# buck-boost.net
KiCad netlist of a schematic drawn in Altium Designer
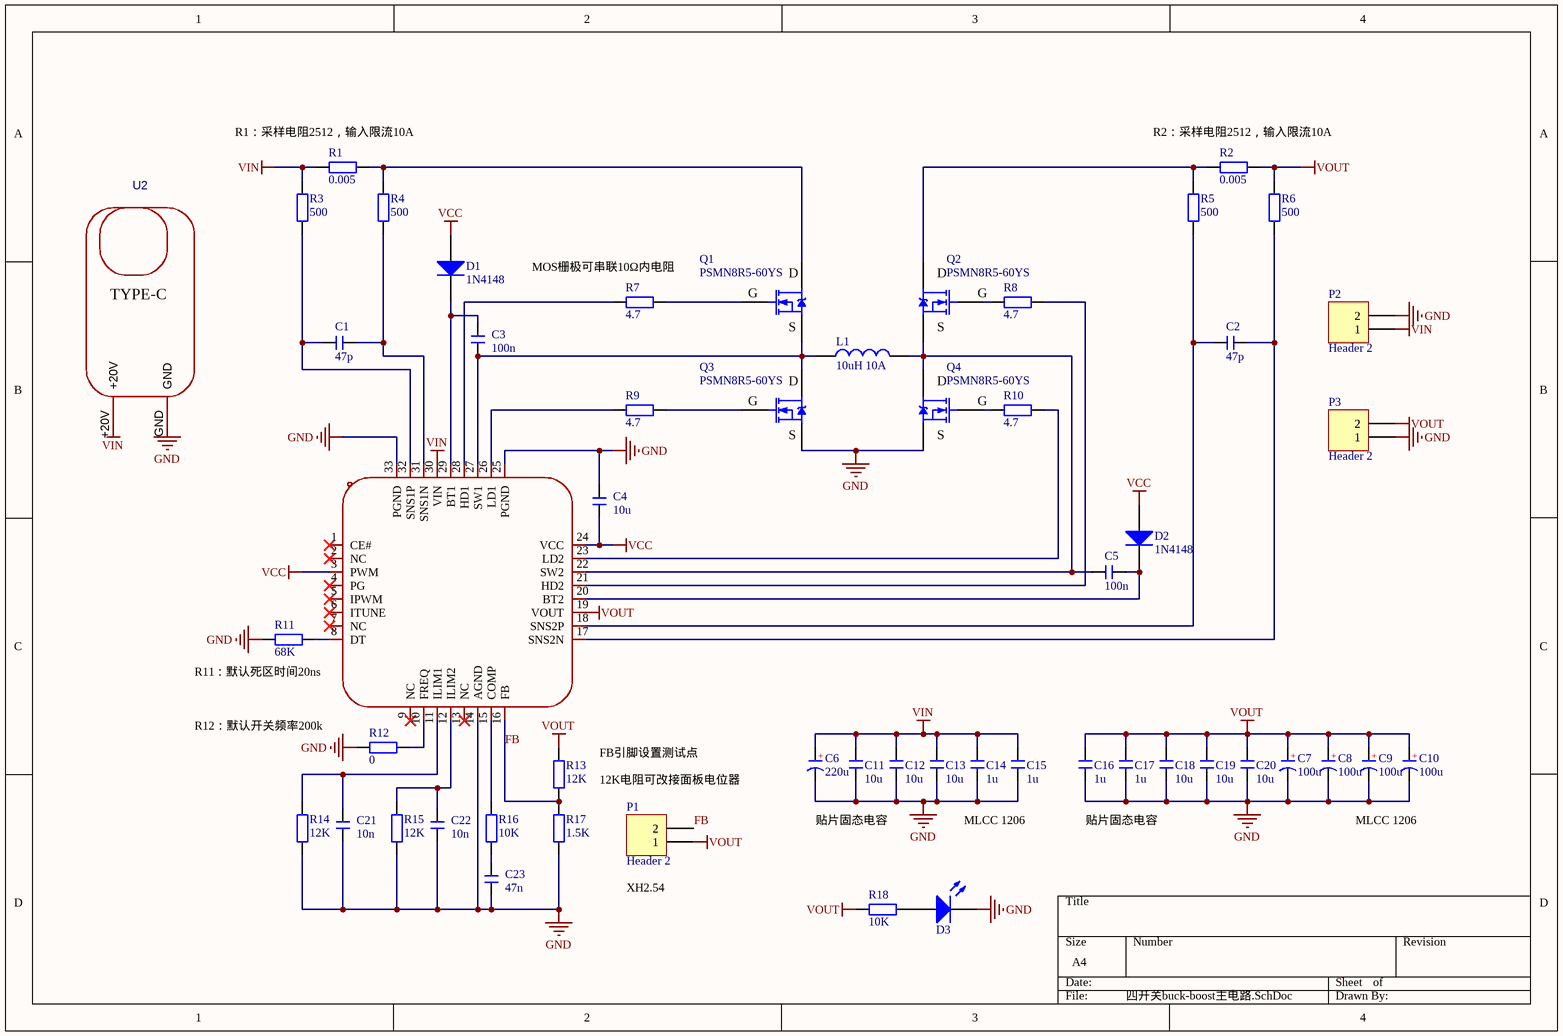
[diagram p0: 四开关buck-boost主电路.SchDoc]

(export (version "E")
  (design (tool "Eeschema 10.0.6"))
  (components
    (comp (ref "C1")
      (value "47p")
      (footprint "C 0603_M")
      (description "贴片电容")
      (libsource (lib "0.1 - 电阻-电容-电感") (part "C"))
    )
    (comp (ref "C2")
      (value "47p")
      (footprint "C 0603_M")
      (description "贴片电容")
      (libsource (lib "0.1 - 电阻-电容-电感") (part "C"))
    )
    (comp (ref "C3")
      (value "100n")
      (footprint "C 0603_M")
      (description "贴片电容")
      (libsource (lib "0.1 - 电阻-电容-电感") (part "C"))
    )
    (comp (ref "C4")
      (value "10u")
      (footprint "C 0603_M")
      (description "贴片电容")
      (libsource (lib "0.1 - 电阻-电容-电感") (part "C"))
    )
    (comp (ref "C5")
      (value "100n")
      (footprint "C 0603_M")
      (description "贴片电容")
      (libsource (lib "0.1 - 电阻-电容-电感") (part "C"))
    )
    (comp (ref "C6")
      (value "220u")
      (footprint "CM F(10*10.2)")
      (description "直插电解电容")
      (libsource (lib "0.1 - 电阻-电容-电感") (part "CE"))
    )
    (comp (ref "C7")
      (value "100u")
      (footprint "CM E(8*10.2)")
      (description "直插电解电容")
      (libsource (lib "0.1 - 电阻-电容-电感") (part "CE"))
    )
    (comp (ref "C8")
      (value "100u")
      (footprint "CM E(8*10.2)")
      (description "直插电解电容")
      (libsource (lib "0.1 - 电阻-电容-电感") (part "CE"))
    )
    (comp (ref "C9")
      (value "100u")
      (footprint "CM E(8*10.2)")
      (description "直插电解电容")
      (libsource (lib "0.1 - 电阻-电容-电感") (part "CE"))
    )
    (comp (ref "C10")
      (value "100u")
      (footprint "CM E(8*10.2)")
      (description "直插电解电容")
      (libsource (lib "0.1 - 电阻-电容-电感") (part "CE"))
    )
    (comp (ref "C11")
      (value "10u")
      (footprint "C 1206_M")
      (description "贴片电容")
      (libsource (lib "0.1 - 电阻-电容-电感") (part "C"))
    )
    (comp (ref "C12")
      (value "10u")
      (footprint "C 1206_M")
      (description "贴片电容")
      (libsource (lib "0.1 - 电阻-电容-电感") (part "C"))
    )
    (comp (ref "C13")
      (value "10u")
      (footprint "C 1206_M")
      (description "贴片电容")
      (libsource (lib "0.1 - 电阻-电容-电感") (part "C"))
    )
    (comp (ref "C14")
      (value "1u")
      (footprint "C 1206_M")
      (description "贴片电容")
      (libsource (lib "0.1 - 电阻-电容-电感") (part "C"))
    )
    (comp (ref "C15")
      (value "1u")
      (footprint "C 1206_M")
      (description "贴片电容")
      (libsource (lib "0.1 - 电阻-电容-电感") (part "C"))
    )
    (comp (ref "C16")
      (value "1u")
      (footprint "C 1206_M")
      (description "贴片电容")
      (libsource (lib "0.1 - 电阻-电容-电感") (part "C"))
    )
    (comp (ref "C17")
      (value "1u")
      (footprint "C 1206_M")
      (description "贴片电容")
      (libsource (lib "0.1 - 电阻-电容-电感") (part "C"))
    )
    (comp (ref "C18")
      (value "10u")
      (footprint "C 1206_M")
      (description "贴片电容")
      (libsource (lib "0.1 - 电阻-电容-电感") (part "C"))
    )
    (comp (ref "C19")
      (value "10u")
      (footprint "C 1206_M")
      (description "贴片电容")
      (libsource (lib "0.1 - 电阻-电容-电感") (part "C"))
    )
    (comp (ref "C20")
      (value "10u")
      (footprint "C 1206_M")
      (description "贴片电容")
      (libsource (lib "0.1 - 电阻-电容-电感") (part "C"))
    )
    (comp (ref "C21")
      (value "10n")
      (footprint "C 0603_M")
      (description "贴片电容")
      (libsource (lib "0.1 - 电阻-电容-电感") (part "C"))
    )
    (comp (ref "C22")
      (value "10n")
      (footprint "C 0603_M")
      (description "贴片电容")
      (libsource (lib "0.1 - 电阻-电容-电感") (part "C"))
    )
    (comp (ref "C23")
      (value "47n")
      (footprint "C 0603_M")
      (description "贴片电容")
      (libsource (lib "0.1 - 电阻-电容-电感") (part "C"))
    )
    (comp (ref "D1")
      (value "1N4148")
      (footprint "SOD-323")
      (description "Default Diode")
      (fields (field (name "PUBLISHER") "Altium Limited"))
      (libsource (lib "Miscellaneous Devices") (part "Diode"))
    )
    (comp (ref "D2")
      (value "1N4148")
      (footprint "SOD-323")
      (description "Default Diode")
      (fields (field (name "PUBLISHER") "Altium Limited"))
      (libsource (lib "Miscellaneous Devices") (part "Diode"))
    )
    (comp (ref "D3")
      (value "LED")
      (footprint "LED 0603G")
      (description "发光二极管")
      (libsource (lib "0.3 - LED发光二极管") (part "LED"))
    )
    (comp (ref "L1")
      (value "10uH 10A")
      (footprint "IND-SMD_L13.8-W12.6_SMMS1360")
      (description "小功率贴片电感")
      (libsource (lib "0.1 - 电阻-电容-电感") (part "L"))
    )
    (comp (ref "P1")
      (value "Header 2")
      (footprint "HDR1X2")
      (description "Header, 2-Pin")
      (fields (field (name "PUBLISHER") "Altium Limited"))
      (libsource (lib "Miscellaneous Connectors") (part "Header 2"))
    )
    (comp (ref "P2")
      (value "Header 2")
      (footprint "CONN-TH_2P-P3.81_WJ15EDGRC-3.81-2P")
      (description "Header, 2-Pin")
      (fields (field (name "PUBLISHER") "Altium Limited"))
      (libsource (lib "Miscellaneous Connectors") (part "Header 2"))
    )
    (comp (ref "P3")
      (value "Header 2")
      (footprint "CONN-TH_2P-P3.81_WJ15EDGRC-3.81-2P")
      (description "Header, 2-Pin")
      (fields (field (name "PUBLISHER") "Altium Limited"))
      (libsource (lib "Miscellaneous Connectors") (part "Header 2"))
    )
    (comp (ref "Q1")
      (value "PSMN8R5-60YS")
      (footprint "SOT669")
      (description "N沟场效应管")
      (libsource (lib "0.5 - 场效应管-可控硅") (part "IRF840"))
    )
    (comp (ref "Q2")
      (value "PSMN8R5-60YS")
      (footprint "SOT669")
      (description "N沟场效应管")
      (libsource (lib "0.5 - 场效应管-可控硅") (part "IRF840"))
    )
    (comp (ref "Q3")
      (value "PSMN8R5-60YS")
      (footprint "SOT669")
      (description "N沟场效应管")
      (libsource (lib "0.5 - 场效应管-可控硅") (part "IRF840"))
    )
    (comp (ref "Q4")
      (value "PSMN8R5-60YS")
      (footprint "SOT669")
      (description "N沟场效应管")
      (libsource (lib "0.5 - 场效应管-可控硅") (part "IRF840"))
    )
    (comp (ref "R1")
      (value "0.005")
      (footprint "R 2512_M")
      (description "贴片电阻")
      (fields (field (name "版权归属") "来自淘宝 ID：黄晶宝石"))
      (libsource (lib "0.1 - 电阻-电容-电感") (part "R"))
    )
    (comp (ref "R2")
      (value "0.005")
      (footprint "R 2512_M")
      (description "贴片电阻")
      (fields (field (name "版权归属") "来自淘宝 ID：黄晶宝石"))
      (libsource (lib "0.1 - 电阻-电容-电感") (part "R"))
    )
    (comp (ref "R3")
      (value "500")
      (footprint "R 0603_M")
      (description "贴片电阻")
      (fields (field (name "版权归属") "来自淘宝 ID：黄晶宝石"))
      (libsource (lib "0.1 - 电阻-电容-电感") (part "R"))
    )
    (comp (ref "R4")
      (value "500")
      (footprint "R 0603_M")
      (description "贴片电阻")
      (fields (field (name "版权归属") "来自淘宝 ID：黄晶宝石"))
      (libsource (lib "0.1 - 电阻-电容-电感") (part "R"))
    )
    (comp (ref "R5")
      (value "500")
      (footprint "R 0603_M")
      (description "贴片电阻")
      (fields (field (name "版权归属") "来自淘宝 ID：黄晶宝石"))
      (libsource (lib "0.1 - 电阻-电容-电感") (part "R"))
    )
    (comp (ref "R6")
      (value "500")
      (footprint "R 0603_M")
      (description "贴片电阻")
      (fields (field (name "版权归属") "来自淘宝 ID：黄晶宝石"))
      (libsource (lib "0.1 - 电阻-电容-电感") (part "R"))
    )
    (comp (ref "R7")
      (value "4.7")
      (footprint "R 0603_M")
      (description "贴片电阻")
      (fields (field (name "版权归属") "来自淘宝 ID：黄晶宝石"))
      (libsource (lib "0.1 - 电阻-电容-电感") (part "R"))
    )
    (comp (ref "R8")
      (value "4.7")
      (footprint "R 0603_M")
      (description "贴片电阻")
      (fields (field (name "版权归属") "来自淘宝 ID：黄晶宝石"))
      (libsource (lib "0.1 - 电阻-电容-电感") (part "R"))
    )
    (comp (ref "R9")
      (value "4.7")
      (footprint "R 0603_M")
      (description "贴片电阻")
      (fields (field (name "版权归属") "来自淘宝 ID：黄晶宝石"))
      (libsource (lib "0.1 - 电阻-电容-电感") (part "R"))
    )
    (comp (ref "R10")
      (value "4.7")
      (footprint "R 0603_M")
      (description "贴片电阻")
      (fields (field (name "版权归属") "来自淘宝 ID：黄晶宝石"))
      (libsource (lib "0.1 - 电阻-电容-电感") (part "R"))
    )
    (comp (ref "R11")
      (value "68K")
      (footprint "R 0603_M")
      (description "贴片电阻")
      (fields (field (name "版权归属") "来自淘宝 ID：黄晶宝石"))
      (libsource (lib "0.1 - 电阻-电容-电感") (part "R"))
    )
    (comp (ref "R12")
      (value "0")
      (footprint "R 0603_M")
      (description "贴片电阻")
      (fields (field (name "版权归属") "来自淘宝 ID：黄晶宝石"))
      (libsource (lib "0.1 - 电阻-电容-电感") (part "R"))
    )
    (comp (ref "R13")
      (value "12K")
      (footprint "R 0603_M")
      (description "贴片电阻")
      (fields (field (name "版权归属") "来自淘宝 ID：黄晶宝石"))
      (libsource (lib "0.1 - 电阻-电容-电感") (part "R"))
    )
    (comp (ref "R14")
      (value "12K")
      (footprint "R 0603_M")
      (description "贴片电阻")
      (fields (field (name "版权归属") "来自淘宝 ID：黄晶宝石"))
      (libsource (lib "0.1 - 电阻-电容-电感") (part "R"))
    )
    (comp (ref "R15")
      (value "12K")
      (footprint "R 0603_M")
      (description "贴片电阻")
      (fields (field (name "版权归属") "来自淘宝 ID：黄晶宝石"))
      (libsource (lib "0.1 - 电阻-电容-电感") (part "R"))
    )
    (comp (ref "R16")
      (value "10K")
      (footprint "R 0603_M")
      (description "贴片电阻")
      (fields (field (name "版权归属") "来自淘宝 ID：黄晶宝石"))
      (libsource (lib "0.1 - 电阻-电容-电感") (part "R"))
    )
    (comp (ref "R17")
      (value "1.5K")
      (footprint "R 0603_M")
      (description "贴片电阻")
      (fields (field (name "版权归属") "来自淘宝 ID：黄晶宝石"))
      (libsource (lib "0.1 - 电阻-电容-电感") (part "R"))
    )
    (comp (ref "R18")
      (value "10K")
      (footprint "R 0603_M")
      (description "贴片电阻")
      (fields (field (name "版权归属") "来自淘宝 ID：黄晶宝石"))
      (libsource (lib "0.1 - 电阻-电容-电感") (part "R"))
    )
    (comp (ref "U1")
      (value "SC8701QDER")
      (footprint "QFN-32_L4.0-W4.0-P0.4-BL-EP2.6")
      (fields (field (name "MANUFACTURER") "SOUTHCHIP(南芯)"))
      (libsource (lib "SC8701QDER") (part "SC8701QDER"))
    )
    (comp (ref "U2")
      (value "PD2.0/3.0诱骗器TYPE-C")
      (footprint "PD2.0/3.0诱骗器")
      (libsource (lib "altium-import") (part "root_1_PD2.0/3.0诱骗器TYPE-C_"))
    )
  )
  (nets
    (net (code "1") (name "/FB") (class "Default")
      (node (ref "P1") (pin "2") (pinfunction "2_2") (pintype "passive"))
      (node (ref "R13") (pin "2") (pinfunction "2_2") (pintype "passive"))
      (node (ref "R17") (pin "2") (pinfunction "2_2") (pintype "passive"))
      (node (ref "U1") (pin "16") (pinfunction "FB_16") (pintype "passive"))
    )
    (net (code "2") (name "GND") (class "Default")
      (node (ref "C10") (pin "2") (pinfunction "K_2") (pintype "passive"))
      (node (ref "C11") (pin "1") (pinfunction "1_1") (pintype "passive"))
      (node (ref "C12") (pin "1") (pinfunction "1_1") (pintype "passive"))
      (node (ref "C13") (pin "1") (pinfunction "1_1") (pintype "passive"))
      (node (ref "C14") (pin "1") (pinfunction "1_1") (pintype "passive"))
      (node (ref "C15") (pin "1") (pinfunction "1_1") (pintype "passive"))
      (node (ref "C16") (pin "1") (pinfunction "1_1") (pintype "passive"))
      (node (ref "C17") (pin "1") (pinfunction "1_1") (pintype "passive"))
      (node (ref "C18") (pin "1") (pinfunction "1_1") (pintype "passive"))
      (node (ref "C19") (pin "1") (pinfunction "1_1") (pintype "passive"))
      (node (ref "C20") (pin "1") (pinfunction "1_1") (pintype "passive"))
      (node (ref "C21") (pin "1") (pinfunction "1_1") (pintype "passive"))
      (node (ref "C22") (pin "1") (pinfunction "1_1") (pintype "passive"))
      (node (ref "C23") (pin "1") (pinfunction "1_1") (pintype "passive"))
      (node (ref "C4") (pin "2") (pinfunction "2_2") (pintype "passive"))
      (node (ref "C6") (pin "2") (pinfunction "K_2") (pintype "passive"))
      (node (ref "C7") (pin "2") (pinfunction "K_2") (pintype "passive"))
      (node (ref "C8") (pin "2") (pinfunction "K_2") (pintype "passive"))
      (node (ref "C9") (pin "2") (pinfunction "K_2") (pintype "passive"))
      (node (ref "D3") (pin "2") (pinfunction "K_2") (pintype "passive"))
      (node (ref "P2") (pin "2") (pinfunction "2_2") (pintype "passive"))
      (node (ref "P3") (pin "1") (pinfunction "1_1") (pintype "passive"))
      (node (ref "Q3") (pin "3") (pinfunction "S_3") (pintype "passive"))
      (node (ref "Q4") (pin "3") (pinfunction "S_3") (pintype "passive"))
      (node (ref "R11") (pin "2") (pinfunction "2_2") (pintype "passive"))
      (node (ref "R12") (pin "2") (pinfunction "2_2") (pintype "passive"))
      (node (ref "R14") (pin "2") (pinfunction "2_2") (pintype "passive"))
      (node (ref "R15") (pin "2") (pinfunction "2_2") (pintype "passive"))
      (node (ref "R17") (pin "1") (pinfunction "1_1") (pintype "passive"))
      (node (ref "U1") (pin "14") (pinfunction "AGND_14") (pintype "passive"))
      (node (ref "U1") (pin "25") (pinfunction "PGND_25") (pintype "passive"))
      (node (ref "U1") (pin "33") (pinfunction "PGND_33") (pintype "passive"))
      (node (ref "U2") (pin "GND") (pinfunction "GND_GND") (pintype "passive"))
    )
    (net (code "3") (name "Net-(C23-Pad2)") (class "Default")
      (node (ref "C23") (pin "2") (pinfunction "2_2") (pintype "passive"))
      (node (ref "R16") (pin "2") (pinfunction "2_2") (pintype "passive"))
    )
    (net (code "4") (name "Net-(D1-K)") (class "Default")
      (node (ref "C3") (pin "2") (pinfunction "2_2") (pintype "passive"))
      (node (ref "D1") (pin "2") (pinfunction "K_2") (pintype "passive"))
      (node (ref "U1") (pin "29") (pinfunction "BT1_29") (pintype "passive"))
    )
    (net (code "5") (name "Net-(D2-K)") (class "Default")
      (node (ref "C5") (pin "1") (pinfunction "1_1") (pintype "passive"))
      (node (ref "D2") (pin "2") (pinfunction "K_2") (pintype "passive"))
      (node (ref "U1") (pin "20") (pinfunction "BT2_20") (pintype "passive"))
    )
    (net (code "6") (name "Net-(D3-A)") (class "Default")
      (node (ref "D3") (pin "1") (pinfunction "A_1") (pintype "passive"))
      (node (ref "R18") (pin "1") (pinfunction "1_1") (pintype "passive"))
    )
    (net (code "7") (name "Net-(Q1-D)") (class "Default")
      (node (ref "Q1") (pin "2") (pinfunction "D_2") (pintype "passive"))
      (node (ref "R1") (pin "2") (pinfunction "2_2") (pintype "passive"))
      (node (ref "R4") (pin "2") (pinfunction "2_2") (pintype "passive"))
    )
    (net (code "8") (name "Net-(Q1-G)") (class "Default")
      (node (ref "Q1") (pin "1") (pinfunction "G_1") (pintype "passive"))
      (node (ref "R7") (pin "2") (pinfunction "2_2") (pintype "passive"))
    )
    (net (code "9") (name "Net-(Q1-S)") (class "Default")
      (node (ref "C3") (pin "1") (pinfunction "1_1") (pintype "passive"))
      (node (ref "L1") (pin "1") (pinfunction "1_1") (pintype "passive"))
      (node (ref "Q1") (pin "3") (pinfunction "S_3") (pintype "passive"))
      (node (ref "Q3") (pin "2") (pinfunction "D_2") (pintype "passive"))
      (node (ref "U1") (pin "27") (pinfunction "SW1_27") (pintype "passive"))
    )
    (net (code "10") (name "Net-(Q2-D)") (class "Default")
      (node (ref "Q2") (pin "2") (pinfunction "D_2") (pintype "passive"))
      (node (ref "R2") (pin "1") (pinfunction "1_1") (pintype "passive"))
      (node (ref "R5") (pin "2") (pinfunction "2_2") (pintype "passive"))
    )
    (net (code "11") (name "Net-(Q2-G)") (class "Default")
      (node (ref "Q2") (pin "1") (pinfunction "G_1") (pintype "passive"))
      (node (ref "R8") (pin "1") (pinfunction "1_1") (pintype "passive"))
    )
    (net (code "12") (name "Net-(Q2-S)") (class "Default")
      (node (ref "C5") (pin "2") (pinfunction "2_2") (pintype "passive"))
      (node (ref "L1") (pin "2") (pinfunction "2_2") (pintype "passive"))
      (node (ref "Q2") (pin "3") (pinfunction "S_3") (pintype "passive"))
      (node (ref "Q4") (pin "2") (pinfunction "D_2") (pintype "passive"))
      (node (ref "U1") (pin "22") (pinfunction "SW2_22") (pintype "passive"))
    )
    (net (code "13") (name "Net-(Q3-G)") (class "Default")
      (node (ref "Q3") (pin "1") (pinfunction "G_1") (pintype "passive"))
      (node (ref "R9") (pin "2") (pinfunction "2_2") (pintype "passive"))
    )
    (net (code "14") (name "Net-(Q4-G)") (class "Default")
      (node (ref "Q4") (pin "1") (pinfunction "G_1") (pintype "passive"))
      (node (ref "R10") (pin "1") (pinfunction "1_1") (pintype "passive"))
    )
    (net (code "15") (name "Net-(U1-COMP)") (class "Default")
      (node (ref "R16") (pin "1") (pinfunction "1_1") (pintype "passive"))
      (node (ref "U1") (pin "15") (pinfunction "COMP_15") (pintype "passive"))
    )
    (net (code "16") (name "Net-(U1-DT)") (class "Default")
      (node (ref "R11") (pin "1") (pinfunction "1_1") (pintype "passive"))
      (node (ref "U1") (pin "8") (pinfunction "DT_8") (pintype "passive"))
    )
    (net (code "17") (name "Net-(U1-FREQ)") (class "Default")
      (node (ref "R12") (pin "1") (pinfunction "1_1") (pintype "passive"))
      (node (ref "U1") (pin "10") (pinfunction "FREQ_10") (pintype "passive"))
    )
    (net (code "18") (name "Net-(U1-HD1)") (class "Default")
      (node (ref "R7") (pin "1") (pinfunction "1_1") (pintype "passive"))
      (node (ref "U1") (pin "28") (pinfunction "HD1_28") (pintype "passive"))
    )
    (net (code "19") (name "Net-(U1-HD2)") (class "Default")
      (node (ref "R8") (pin "2") (pinfunction "2_2") (pintype "passive"))
      (node (ref "U1") (pin "21") (pinfunction "HD2_21") (pintype "passive"))
    )
    (net (code "20") (name "Net-(U1-ILIM1)") (class "Default")
      (node (ref "C21") (pin "2") (pinfunction "2_2") (pintype "passive"))
      (node (ref "R14") (pin "1") (pinfunction "1_1") (pintype "passive"))
      (node (ref "U1") (pin "11") (pinfunction "ILIM1_11") (pintype "passive"))
    )
    (net (code "21") (name "Net-(U1-ILIM2)") (class "Default")
      (node (ref "C22") (pin "2") (pinfunction "2_2") (pintype "passive"))
      (node (ref "R15") (pin "1") (pinfunction "1_1") (pintype "passive"))
      (node (ref "U1") (pin "12") (pinfunction "ILIM2_12") (pintype "passive"))
    )
    (net (code "22") (name "Net-(U1-LD1)") (class "Default")
      (node (ref "R9") (pin "1") (pinfunction "1_1") (pintype "passive"))
      (node (ref "U1") (pin "26") (pinfunction "LD1_26") (pintype "passive"))
    )
    (net (code "23") (name "Net-(U1-LD2)") (class "Default")
      (node (ref "R10") (pin "2") (pinfunction "2_2") (pintype "passive"))
      (node (ref "U1") (pin "23") (pinfunction "LD2_23") (pintype "passive"))
    )
    (net (code "24") (name "Net-(U1-SNS1N)") (class "Default")
      (node (ref "C1") (pin "1") (pinfunction "1_1") (pintype "passive"))
      (node (ref "R4") (pin "1") (pinfunction "1_1") (pintype "passive"))
      (node (ref "U1") (pin "31") (pinfunction "SNS1N_31") (pintype "passive"))
    )
    (net (code "25") (name "Net-(U1-SNS1P)") (class "Default")
      (node (ref "C1") (pin "2") (pinfunction "2_2") (pintype "passive"))
      (node (ref "R3") (pin "1") (pinfunction "1_1") (pintype "passive"))
      (node (ref "U1") (pin "32") (pinfunction "SNS1P_32") (pintype "passive"))
    )
    (net (code "26") (name "Net-(U1-SNS2N)") (class "Default")
      (node (ref "C2") (pin "1") (pinfunction "1_1") (pintype "passive"))
      (node (ref "R6") (pin "1") (pinfunction "1_1") (pintype "passive"))
      (node (ref "U1") (pin "17") (pinfunction "SNS2N_17") (pintype "passive"))
    )
    (net (code "27") (name "Net-(U1-SNS2P)") (class "Default")
      (node (ref "C2") (pin "2") (pinfunction "2_2") (pintype "passive"))
      (node (ref "R5") (pin "1") (pinfunction "1_1") (pintype "passive"))
      (node (ref "U1") (pin "18") (pinfunction "SNS2P_18") (pintype "passive"))
    )
    (net (code "28") (name "VCC") (class "Default")
      (node (ref "C4") (pin "1") (pinfunction "1_1") (pintype "passive"))
      (node (ref "D1") (pin "1") (pinfunction "A_1") (pintype "passive"))
      (node (ref "D2") (pin "1") (pinfunction "A_1") (pintype "passive"))
      (node (ref "U1") (pin "24") (pinfunction "VCC_24") (pintype "passive"))
      (node (ref "U1") (pin "3") (pinfunction "PWM_3") (pintype "passive"))
    )
    (net (code "29") (name "VIN") (class "Default")
      (node (ref "C11") (pin "2") (pinfunction "2_2") (pintype "passive"))
      (node (ref "C12") (pin "2") (pinfunction "2_2") (pintype "passive"))
      (node (ref "C13") (pin "2") (pinfunction "2_2") (pintype "passive"))
      (node (ref "C14") (pin "2") (pinfunction "2_2") (pintype "passive"))
      (node (ref "C15") (pin "2") (pinfunction "2_2") (pintype "passive"))
      (node (ref "C6") (pin "1") (pinfunction "A_1") (pintype "passive"))
      (node (ref "P2") (pin "1") (pinfunction "1_1") (pintype "passive"))
      (node (ref "R1") (pin "1") (pinfunction "1_1") (pintype "passive"))
      (node (ref "R3") (pin "2") (pinfunction "2_2") (pintype "passive"))
      (node (ref "U1") (pin "30") (pinfunction "VIN_30") (pintype "passive"))
      (node (ref "U2") (pin "+20V") (pinfunction "+20V_+20V") (pintype "passive"))
    )
    (net (code "30") (name "VOUT") (class "Default")
      (node (ref "C10") (pin "1") (pinfunction "A_1") (pintype "passive"))
      (node (ref "C16") (pin "2") (pinfunction "2_2") (pintype "passive"))
      (node (ref "C17") (pin "2") (pinfunction "2_2") (pintype "passive"))
      (node (ref "C18") (pin "2") (pinfunction "2_2") (pintype "passive"))
      (node (ref "C19") (pin "2") (pinfunction "2_2") (pintype "passive"))
      (node (ref "C20") (pin "2") (pinfunction "2_2") (pintype "passive"))
      (node (ref "C7") (pin "1") (pinfunction "A_1") (pintype "passive"))
      (node (ref "C8") (pin "1") (pinfunction "A_1") (pintype "passive"))
      (node (ref "C9") (pin "1") (pinfunction "A_1") (pintype "passive"))
      (node (ref "P1") (pin "1") (pinfunction "1_1") (pintype "passive"))
      (node (ref "P3") (pin "2") (pinfunction "2_2") (pintype "passive"))
      (node (ref "R13") (pin "1") (pinfunction "1_1") (pintype "passive"))
      (node (ref "R18") (pin "2") (pinfunction "2_2") (pintype "passive"))
      (node (ref "R2") (pin "2") (pinfunction "2_2") (pintype "passive"))
      (node (ref "R6") (pin "2") (pinfunction "2_2") (pintype "passive"))
      (node (ref "U1") (pin "19") (pinfunction "VOUT_19") (pintype "passive"))
    )
    (net (code "31") (name "unconnected-(U1-CE#-Pad1)") (class "Default")
      (node (ref "U1") (pin "1") (pinfunction "CE#_1") (pintype "passive+no_connect"))
    )
    (net (code "32") (name "unconnected-(U1-IPWM-Pad5)") (class "Default")
      (node (ref "U1") (pin "5") (pinfunction "IPWM_5") (pintype "passive+no_connect"))
    )
    (net (code "33") (name "unconnected-(U1-ITUNE-Pad6)") (class "Default")
      (node (ref "U1") (pin "6") (pinfunction "ITUNE_6") (pintype "passive+no_connect"))
    )
    (net (code "34") (name "unconnected-(U1-NC-Pad2)") (class "Default")
      (node (ref "U1") (pin "2") (pinfunction "NC_2") (pintype "passive+no_connect"))
    )
    (net (code "35") (name "unconnected-(U1-NC-Pad7)") (class "Default")
      (node (ref "U1") (pin "7") (pinfunction "NC_7") (pintype "passive+no_connect"))
    )
    (net (code "36") (name "unconnected-(U1-NC-Pad9)") (class "Default")
      (node (ref "U1") (pin "9") (pinfunction "NC_9") (pintype "passive+no_connect"))
    )
    (net (code "37") (name "unconnected-(U1-NC-Pad13)") (class "Default")
      (node (ref "U1") (pin "13") (pinfunction "NC_13") (pintype "passive+no_connect"))
    )
    (net (code "38") (name "unconnected-(U1-PG-Pad4)") (class "Default")
      (node (ref "U1") (pin "4") (pinfunction "PG_4") (pintype "passive+no_connect"))
    )
  )
)
